# leonino.net
KiCad netlist of a schematic drawn in EAGLE
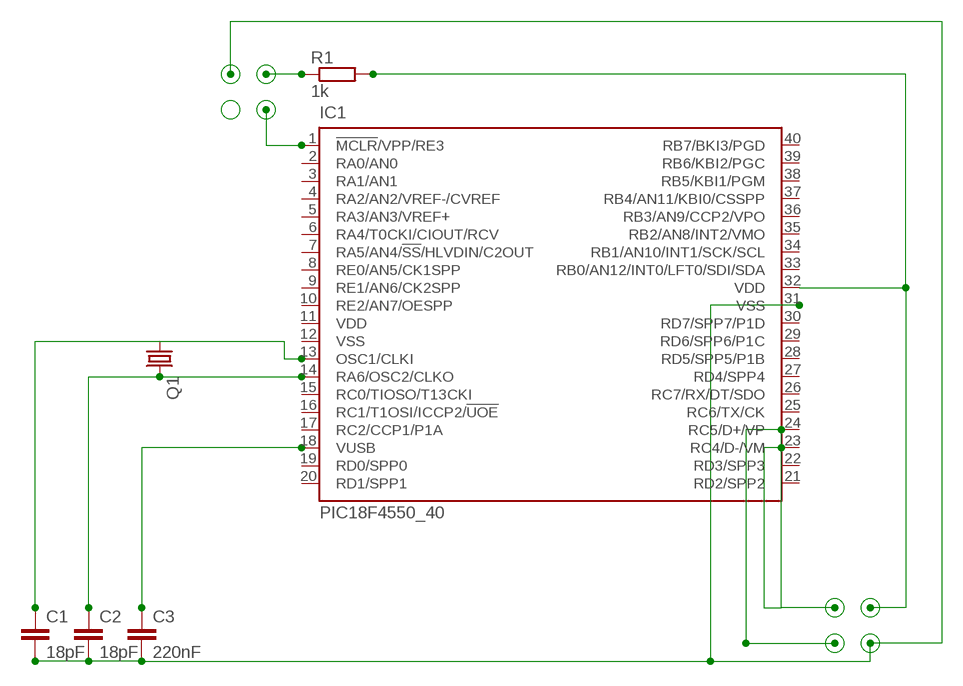
[diagram p0: schematic, sheet 1]

(export (version "E")
  (design (tool "Eeschema 10.0.6"))
  (components
    (comp (ref "C1")
      (value "18pF")
      (footprint "eagle-import:C025-025X050")
      (libsource (lib "eagle-import") (part "C-EU025-025X050"))
    )
    (comp (ref "C2")
      (value "18pF")
      (footprint "eagle-import:C025-025X050")
      (libsource (lib "eagle-import") (part "C-EU025-025X050"))
    )
    (comp (ref "C3")
      (value "220nF")
      (footprint "eagle-import:C025-025X050")
      (libsource (lib "eagle-import") (part "C-EU025-025X050"))
    )
    (comp (ref "IC1")
      (value "PIC18F4550_40")
      (footprint "eagle-import:DIL40")
      (fields (field (name "MF") "MICROCHIP") (field (name "MPN") "PIC18F4550-I/P"))
      (libsource (lib "eagle-import") (part "PIC18F4_40550"))
    )
    (comp (ref "Q1")
      (value "CRYSTALHC49S")
      (footprint "eagle-import:HC49_S")
      (libsource (lib "eagle-import") (part "CRYSTALHC49S"))
    )
    (comp (ref "R1")
      (value "1k")
      (footprint "eagle-import:0204_5")
      (libsource (lib "eagle-import") (part "R-EU_0204/5"))
    )
  )
  (nets
    (net (code "1") (name "/VDD") (class "Default")
      (node (ref "IC1") (pin "11") (pinfunction "VDD_11") (pintype "power_in"))
    )
    (net (code "2") (name "/VSS") (class "Default")
      (node (ref "IC1") (pin "12") (pinfunction "VSS_12") (pintype "power_in"))
    )
    (net (code "3") (name "Net-(C1-Pad2)") (class "Default")
      (node (ref "C1") (pin "2") (pinfunction "2_2") (pintype "passive"))
      (node (ref "C2") (pin "2") (pinfunction "2_2") (pintype "passive"))
      (node (ref "C3") (pin "2") (pinfunction "2_2") (pintype "passive"))
      (node (ref "IC1") (pin "31") (pinfunction "VSS_31") (pintype "power_in"))
    )
    (net (code "4") (name "Net-(IC1-OSC1{slash}CLKI)") (class "Default")
      (node (ref "C1") (pin "1") (pinfunction "1_1") (pintype "passive"))
      (node (ref "IC1") (pin "13") (pinfunction "OSC1/CLKI_13") (pintype "input"))
    )
    (net (code "5") (name "Net-(IC1-RA6{slash}OSC2{slash}CLKO)") (class "Default")
      (node (ref "C2") (pin "1") (pinfunction "1_1") (pintype "passive"))
      (node (ref "IC1") (pin "14") (pinfunction "RA6/OSC2/CLKO_14") (pintype "output"))
      (node (ref "Q1") (pin "2") (pinfunction "2_2") (pintype "passive"))
    )
    (net (code "6") (name "Net-(IC1-VDD-Pad32)") (class "Default")
      (node (ref "IC1") (pin "32") (pinfunction "VDD_32") (pintype "power_in"))
      (node (ref "R1") (pin "2") (pinfunction "2_2") (pintype "passive"))
    )
    (net (code "7") (name "Net-(IC1-VUSB)") (class "Default")
      (node (ref "C3") (pin "1") (pinfunction "1_1") (pintype "passive"))
      (node (ref "IC1") (pin "18") (pinfunction "VUSB_18") (pintype "bidirectional"))
    )
    (net (code "8") (name "unconnected-(IC1-RA0{slash}AN0-Pad2)") (class "Default")
      (node (ref "IC1") (pin "2") (pinfunction "RA0/AN0_2") (pintype "bidirectional"))
    )
    (net (code "9") (name "unconnected-(IC1-RA1{slash}AN1-Pad3)") (class "Default")
      (node (ref "IC1") (pin "3") (pinfunction "RA1/AN1_3") (pintype "bidirectional"))
    )
    (net (code "10") (name "unconnected-(IC1-RA2{slash}AN2{slash}VREF-{slash}CVREF-Pad4)") (class "Default")
      (node (ref "IC1") (pin "4") (pinfunction "RA2/AN2/VREF-/CVREF_4") (pintype "bidirectional"))
    )
    (net (code "11") (name "unconnected-(IC1-RA3{slash}AN3{slash}VREF+-Pad5)") (class "Default")
      (node (ref "IC1") (pin "5") (pinfunction "RA3/AN3/VREF+_5") (pintype "bidirectional"))
    )
    (net (code "12") (name "unconnected-(IC1-RA4{slash}T0CKI{slash}CIOUT{slash}RCV-Pad6)") (class "Default")
      (node (ref "IC1") (pin "6") (pinfunction "RA4/T0CKI/CIOUT/RCV_6") (pintype "bidirectional"))
    )
    (net (code "13") (name "unconnected-(IC1-RA5{slash}AN4{slash}~{SS}{slash}HLVDIN{slash}C2OUT-Pad7)") (class "Default")
      (node (ref "IC1") (pin "7") (pinfunction "RA5/AN4/~{SS}/HLVDIN/C2OUT_7") (pintype "bidirectional"))
    )
    (net (code "14") (name "unconnected-(IC1-RB0{slash}AN12{slash}INT0{slash}LFT0{slash}SDI{slash}SDA-Pad33)") (class "Default")
      (node (ref "IC1") (pin "33") (pinfunction "RB0/AN12/INT0/LFT0/SDI/SDA_33") (pintype "bidirectional"))
    )
    (net (code "15") (name "unconnected-(IC1-RB1{slash}AN10{slash}INT1{slash}SCK{slash}SCL-Pad34)") (class "Default")
      (node (ref "IC1") (pin "34") (pinfunction "RB1/AN10/INT1/SCK/SCL_34") (pintype "bidirectional"))
    )
    (net (code "16") (name "unconnected-(IC1-RB2{slash}AN8{slash}INT2{slash}VMO-Pad35)") (class "Default")
      (node (ref "IC1") (pin "35") (pinfunction "RB2/AN8/INT2/VMO_35") (pintype "bidirectional"))
    )
    (net (code "17") (name "unconnected-(IC1-RB3{slash}AN9{slash}CCP2{slash}VPO-Pad36)") (class "Default")
      (node (ref "IC1") (pin "36") (pinfunction "RB3/AN9/CCP2/VPO_36") (pintype "bidirectional"))
    )
    (net (code "18") (name "unconnected-(IC1-RB4{slash}AN11{slash}KBI0{slash}CSSPP-Pad37)") (class "Default")
      (node (ref "IC1") (pin "37") (pinfunction "RB4/AN11/KBI0/CSSPP_37") (pintype "bidirectional"))
    )
    (net (code "19") (name "unconnected-(IC1-RB5{slash}KBI1{slash}PGM-Pad38)") (class "Default")
      (node (ref "IC1") (pin "38") (pinfunction "RB5/KBI1/PGM_38") (pintype "bidirectional"))
    )
    (net (code "20") (name "unconnected-(IC1-RB6{slash}KBI2{slash}PGC-Pad39)") (class "Default")
      (node (ref "IC1") (pin "39") (pinfunction "RB6/KBI2/PGC_39") (pintype "bidirectional"))
    )
    (net (code "21") (name "unconnected-(IC1-RB7{slash}BKI3{slash}PGD-Pad40)") (class "Default")
      (node (ref "IC1") (pin "40") (pinfunction "RB7/BKI3/PGD_40") (pintype "bidirectional"))
    )
    (net (code "22") (name "unconnected-(IC1-RC0{slash}TIOSO{slash}T13CKI-Pad15)") (class "Default")
      (node (ref "IC1") (pin "15") (pinfunction "RC0/TIOSO/T13CKI_15") (pintype "bidirectional"))
    )
    (net (code "23") (name "unconnected-(IC1-RC1{slash}T1OSI{slash}ICCP2{slash}~{UOE}-Pad16)") (class "Default")
      (node (ref "IC1") (pin "16") (pinfunction "RC1/T1OSI/ICCP2/~{UOE}_16") (pintype "bidirectional"))
    )
    (net (code "24") (name "unconnected-(IC1-RC2{slash}CCP1{slash}P1A-Pad17)") (class "Default")
      (node (ref "IC1") (pin "17") (pinfunction "RC2/CCP1/P1A_17") (pintype "bidirectional"))
    )
    (net (code "25") (name "unconnected-(IC1-RC4{slash}D-{slash}VM-Pad23)") (class "Default")
      (node (ref "IC1") (pin "23") (pinfunction "RC4/D-/VM_23") (pintype "bidirectional"))
    )
    (net (code "26") (name "unconnected-(IC1-RC5{slash}D+{slash}VP-Pad24)") (class "Default")
      (node (ref "IC1") (pin "24") (pinfunction "RC5/D+/VP_24") (pintype "bidirectional"))
    )
    (net (code "27") (name "unconnected-(IC1-RC6{slash}TX{slash}CK-Pad25)") (class "Default")
      (node (ref "IC1") (pin "25") (pinfunction "RC6/TX/CK_25") (pintype "bidirectional"))
    )
    (net (code "28") (name "unconnected-(IC1-RC7{slash}RX{slash}DT{slash}SDO-Pad26)") (class "Default")
      (node (ref "IC1") (pin "26") (pinfunction "RC7/RX/DT/SDO_26") (pintype "bidirectional"))
    )
    (net (code "29") (name "unconnected-(IC1-RD0{slash}SPP0-Pad19)") (class "Default")
      (node (ref "IC1") (pin "19") (pinfunction "RD0/SPP0_19") (pintype "bidirectional"))
    )
    (net (code "30") (name "unconnected-(IC1-RD1{slash}SPP1-Pad20)") (class "Default")
      (node (ref "IC1") (pin "20") (pinfunction "RD1/SPP1_20") (pintype "bidirectional"))
    )
    (net (code "31") (name "unconnected-(IC1-RD2{slash}SPP2-Pad21)") (class "Default")
      (node (ref "IC1") (pin "21") (pinfunction "RD2/SPP2_21") (pintype "bidirectional"))
    )
    (net (code "32") (name "unconnected-(IC1-RD3{slash}SPP3-Pad22)") (class "Default")
      (node (ref "IC1") (pin "22") (pinfunction "RD3/SPP3_22") (pintype "bidirectional"))
    )
    (net (code "33") (name "unconnected-(IC1-RD4{slash}SPP4-Pad27)") (class "Default")
      (node (ref "IC1") (pin "27") (pinfunction "RD4/SPP4_27") (pintype "bidirectional"))
    )
    (net (code "34") (name "unconnected-(IC1-RD5{slash}SPP5{slash}P1B-Pad28)") (class "Default")
      (node (ref "IC1") (pin "28") (pinfunction "RD5/SPP5/P1B_28") (pintype "bidirectional"))
    )
    (net (code "35") (name "unconnected-(IC1-RD6{slash}SPP6{slash}P1C-Pad29)") (class "Default")
      (node (ref "IC1") (pin "29") (pinfunction "RD6/SPP6/P1C_29") (pintype "bidirectional"))
    )
    (net (code "36") (name "unconnected-(IC1-RD7{slash}SPP7{slash}P1D-Pad30)") (class "Default")
      (node (ref "IC1") (pin "30") (pinfunction "RD7/SPP7/P1D_30") (pintype "bidirectional"))
    )
    (net (code "37") (name "unconnected-(IC1-RE0{slash}AN5{slash}CK1SPP-Pad8)") (class "Default")
      (node (ref "IC1") (pin "8") (pinfunction "RE0/AN5/CK1SPP_8") (pintype "bidirectional"))
    )
    (net (code "38") (name "unconnected-(IC1-RE1{slash}AN6{slash}CK2SPP-Pad9)") (class "Default")
      (node (ref "IC1") (pin "9") (pinfunction "RE1/AN6/CK2SPP_9") (pintype "bidirectional"))
    )
    (net (code "39") (name "unconnected-(IC1-RE2{slash}AN7{slash}OESPP-Pad10)") (class "Default")
      (node (ref "IC1") (pin "10") (pinfunction "RE2/AN7/OESPP_10") (pintype "bidirectional"))
    )
    (net (code "40") (name "unconnected-(IC1-~{MCLR}{slash}VPP{slash}RE3-Pad1)") (class "Default")
      (node (ref "IC1") (pin "1") (pinfunction "~{MCLR}/VPP/RE3_1") (pintype "input"))
    )
    (net (code "41") (name "unconnected-(Q1-Pad1)") (class "Default")
      (node (ref "Q1") (pin "1") (pinfunction "1_1") (pintype "passive"))
    )
    (net (code "42") (name "unconnected-(R1-Pad1)") (class "Default")
      (node (ref "R1") (pin "1") (pinfunction "1_1") (pintype "passive"))
    )
  )
)
